# minimega.net
KiCad netlist of a schematic drawn in EAGLE
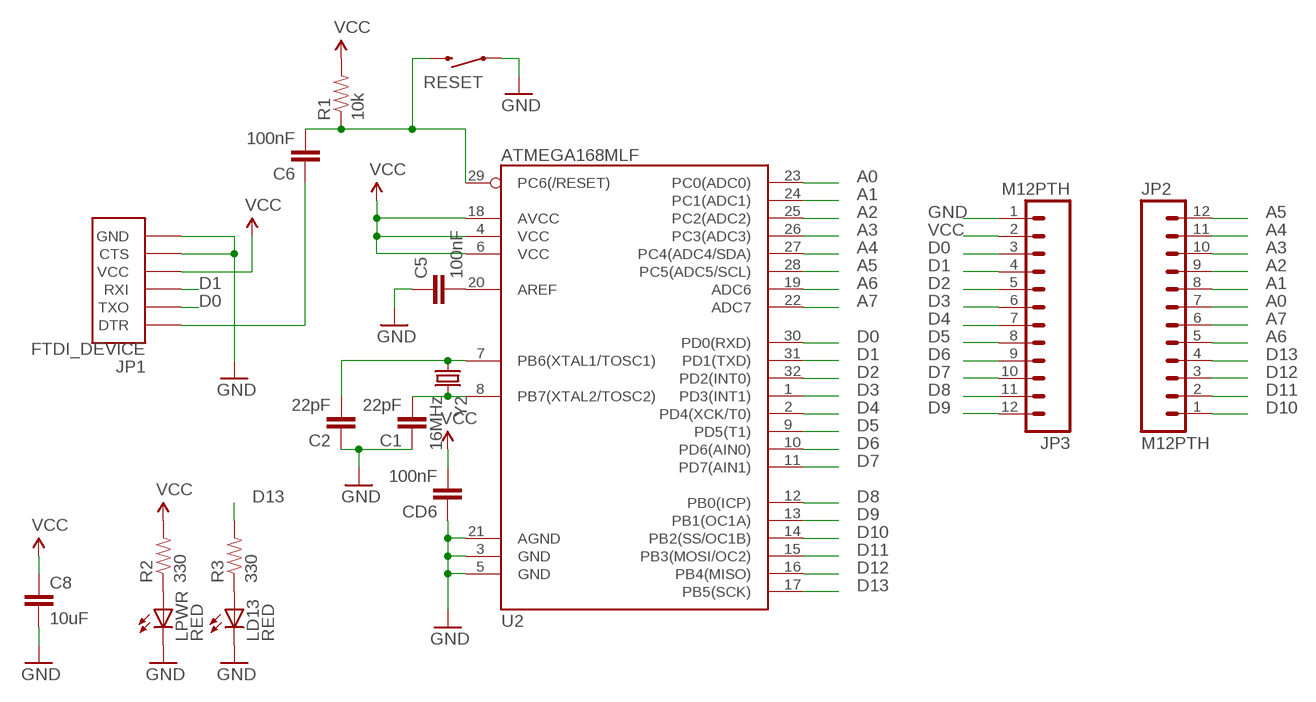
[diagram p0: schematic, sheet 1]

(export (version "E")
  (design (tool "Eeschema 10.0.6"))
  (components
    (comp (ref "C1")
      (value "22pF")
      (footprint "eagle-import:0402-CAP")
      (libsource (lib "eagle-import") (part "10NF-CER"))
    )
    (comp (ref "C2")
      (value "22pF")
      (footprint "eagle-import:0402-CAP")
      (libsource (lib "eagle-import") (part "10NF-CER"))
    )
    (comp (ref "C5")
      (value "100nF")
      (footprint "eagle-import:0402-CAP")
      (libsource (lib "eagle-import") (part "10NF-CER"))
    )
    (comp (ref "C6")
      (value "100nF")
      (footprint "eagle-import:0402-CAP")
      (libsource (lib "eagle-import") (part "10NF-CER"))
    )
    (comp (ref "C8")
      (value "10uF")
      (footprint "eagle-import:0805")
      (libsource (lib "eagle-import") (part "CAP0805"))
    )
    (comp (ref "CD6")
      (value "100nF")
      (footprint "eagle-import:0402-CAP")
      (libsource (lib "eagle-import") (part "10NF-CER"))
    )
    (comp (ref "JP1")
      (value "FTDI_DEVICE")
      (footprint "eagle-import:FTDI_DEVICE_SIDE")
      (libsource (lib "eagle-import") (part "FTDI_DEVICE"))
    )
    (comp (ref "JP2")
      (value "M12PTH")
      (footprint "eagle-import:1X12")
      (libsource (lib "eagle-import") (part "M12PTH"))
    )
    (comp (ref "JP3")
      (value "M12PTH")
      (footprint "eagle-import:1X12")
      (libsource (lib "eagle-import") (part "M12PTH"))
    )
    (comp (ref "LD13")
      (value "RED")
      (footprint "eagle-import:LED-0603")
      (libsource (lib "eagle-import") (part "LED-RED0603"))
    )
    (comp (ref "LPWR")
      (value "RED")
      (footprint "eagle-import:LED-0603")
      (libsource (lib "eagle-import") (part "LED-RED0603"))
    )
    (comp (ref "R1")
      (value "10k")
      (footprint "eagle-import:0603-RES")
      (libsource (lib "eagle-import") (part "RESISTOR0603"))
    )
    (comp (ref "R2")
      (value "330")
      (footprint "eagle-import:0603-RES")
      (libsource (lib "eagle-import") (part "RESISTOR0603"))
    )
    (comp (ref "R3")
      (value "330")
      (footprint "eagle-import:0603-RES")
      (libsource (lib "eagle-import") (part "RESISTOR0603"))
    )
    (comp (ref "RESET")
      (value "SWITCH-MOMENTARY-2PTH")
      (footprint "eagle-import:TACTILE-PTH")
      (libsource (lib "eagle-import") (part "SWITCH-MOMENTARY-2PTH"))
    )
    (comp (ref "U2")
      (value "ATMEGA168MLF")
      (footprint "eagle-import:MLF32")
      (libsource (lib "eagle-import") (part "ATMEGA168MLF"))
    )
    (comp (ref "Y2")
      (value "16MHz")
      (footprint "eagle-import:HC49UP")
      (libsource (lib "eagle-import") (part "CRYSTALSMD"))
    )
  )
  (nets
    (net (code "1") (name "/A0") (class "Default")
      (node (ref "JP2") (pin "7") (pinfunction "7_7") (pintype "passive"))
      (node (ref "U2") (pin "23") (pinfunction "PC0(ADC0)_23") (pintype "bidirectional"))
    )
    (net (code "2") (name "/A1") (class "Default")
      (node (ref "JP2") (pin "8") (pinfunction "8_8") (pintype "passive"))
      (node (ref "U2") (pin "24") (pinfunction "PC1(ADC1)_24") (pintype "bidirectional"))
    )
    (net (code "3") (name "/A2") (class "Default")
      (node (ref "JP2") (pin "9") (pinfunction "9_9") (pintype "passive"))
      (node (ref "U2") (pin "25") (pinfunction "PC2(ADC2)_25") (pintype "bidirectional"))
    )
    (net (code "4") (name "/A3") (class "Default")
      (node (ref "JP2") (pin "10") (pinfunction "10_10") (pintype "passive"))
      (node (ref "U2") (pin "26") (pinfunction "PC3(ADC3)_26") (pintype "bidirectional"))
    )
    (net (code "5") (name "/A4") (class "Default")
      (node (ref "JP2") (pin "11") (pinfunction "11_11") (pintype "passive"))
      (node (ref "U2") (pin "27") (pinfunction "PC4(ADC4/SDA)_27") (pintype "bidirectional"))
    )
    (net (code "6") (name "/A5") (class "Default")
      (node (ref "JP2") (pin "12") (pinfunction "12_12") (pintype "passive"))
      (node (ref "U2") (pin "28") (pinfunction "PC5(ADC5/SCL)_28") (pintype "bidirectional"))
    )
    (net (code "7") (name "/A6") (class "Default")
      (node (ref "JP2") (pin "5") (pinfunction "5_5") (pintype "passive"))
      (node (ref "U2") (pin "19") (pinfunction "ADC6_19") (pintype "bidirectional"))
    )
    (net (code "8") (name "/A7") (class "Default")
      (node (ref "JP2") (pin "6") (pinfunction "6_6") (pintype "passive"))
      (node (ref "U2") (pin "22") (pinfunction "ADC7_22") (pintype "bidirectional"))
    )
    (net (code "9") (name "/D0") (class "Default")
      (node (ref "JP1") (pin "P$2") (pinfunction "TXO_P$2") (pintype "bidirectional"))
      (node (ref "JP3") (pin "3") (pinfunction "3_3") (pintype "passive"))
      (node (ref "U2") (pin "30") (pinfunction "PD0(RXD)_30") (pintype "bidirectional"))
    )
    (net (code "10") (name "/D1") (class "Default")
      (node (ref "JP1") (pin "P$3") (pinfunction "RXI_P$3") (pintype "bidirectional"))
      (node (ref "JP3") (pin "4") (pinfunction "4_4") (pintype "passive"))
      (node (ref "U2") (pin "31") (pinfunction "PD1(TXD)_31") (pintype "bidirectional"))
    )
    (net (code "11") (name "/D2") (class "Default")
      (node (ref "JP3") (pin "5") (pinfunction "5_5") (pintype "passive"))
      (node (ref "U2") (pin "32") (pinfunction "PD2(INT0)_32") (pintype "bidirectional"))
    )
    (net (code "12") (name "/D3") (class "Default")
      (node (ref "JP3") (pin "6") (pinfunction "6_6") (pintype "passive"))
      (node (ref "U2") (pin "1") (pinfunction "PD3(INT1)_1") (pintype "bidirectional"))
    )
    (net (code "13") (name "/D4") (class "Default")
      (node (ref "JP3") (pin "7") (pinfunction "7_7") (pintype "passive"))
      (node (ref "U2") (pin "2") (pinfunction "PD4(XCK/T0)_2") (pintype "bidirectional"))
    )
    (net (code "14") (name "/D5") (class "Default")
      (node (ref "JP3") (pin "8") (pinfunction "8_8") (pintype "passive"))
      (node (ref "U2") (pin "9") (pinfunction "PD5(T1)_9") (pintype "bidirectional"))
    )
    (net (code "15") (name "/D6") (class "Default")
      (node (ref "JP3") (pin "9") (pinfunction "9_9") (pintype "passive"))
      (node (ref "U2") (pin "10") (pinfunction "PD6(AIN0)_10") (pintype "bidirectional"))
    )
    (net (code "16") (name "/D7") (class "Default")
      (node (ref "JP3") (pin "10") (pinfunction "10_10") (pintype "passive"))
      (node (ref "U2") (pin "11") (pinfunction "PD7(AIN1)_11") (pintype "bidirectional"))
    )
    (net (code "17") (name "/D8") (class "Default")
      (node (ref "JP3") (pin "11") (pinfunction "11_11") (pintype "passive"))
      (node (ref "U2") (pin "12") (pinfunction "PB0(ICP)_12") (pintype "bidirectional"))
    )
    (net (code "18") (name "/D9") (class "Default")
      (node (ref "JP3") (pin "12") (pinfunction "12_12") (pintype "passive"))
      (node (ref "U2") (pin "13") (pinfunction "PB1(OC1A)_13") (pintype "bidirectional"))
    )
    (net (code "19") (name "/D10") (class "Default")
      (node (ref "JP2") (pin "1") (pinfunction "1_1") (pintype "passive"))
      (node (ref "U2") (pin "14") (pinfunction "PB2(SS/OC1B)_14") (pintype "bidirectional"))
    )
    (net (code "20") (name "/D11") (class "Default")
      (node (ref "JP2") (pin "2") (pinfunction "2_2") (pintype "passive"))
      (node (ref "U2") (pin "15") (pinfunction "PB3(MOSI/OC2)_15") (pintype "bidirectional"))
    )
    (net (code "21") (name "/D12") (class "Default")
      (node (ref "JP2") (pin "3") (pinfunction "3_3") (pintype "passive"))
      (node (ref "U2") (pin "16") (pinfunction "PB4(MISO)_16") (pintype "bidirectional"))
    )
    (net (code "22") (name "/D13") (class "Default")
      (node (ref "JP2") (pin "4") (pinfunction "4_4") (pintype "passive"))
      (node (ref "R3") (pin "2") (pinfunction "2_2") (pintype "passive"))
      (node (ref "U2") (pin "17") (pinfunction "PB5(SCK)_17") (pintype "bidirectional"))
    )
    (net (code "23") (name "GND") (class "Default")
      (node (ref "C1") (pin "1") (pinfunction "1_1") (pintype "passive"))
      (node (ref "C2") (pin "1") (pinfunction "1_1") (pintype "passive"))
      (node (ref "C5") (pin "1") (pinfunction "1_1") (pintype "passive"))
      (node (ref "C8") (pin "2") (pinfunction "2_2") (pintype "passive"))
      (node (ref "CD6") (pin "1") (pinfunction "1_1") (pintype "passive"))
      (node (ref "JP1") (pin "P$5") (pinfunction "CTS_P$5") (pintype "bidirectional"))
      (node (ref "JP1") (pin "P$6") (pinfunction "GND_P$6") (pintype "bidirectional"))
      (node (ref "JP3") (pin "1") (pinfunction "1_1") (pintype "passive"))
      (node (ref "LD13") (pin "C") (pinfunction "C_C") (pintype "passive"))
      (node (ref "LPWR") (pin "C") (pinfunction "C_C") (pintype "passive"))
      (node (ref "RESET") (pin "1") (pinfunction "1_1") (pintype "passive"))
      (node (ref "U2") (pin "21") (pinfunction "AGND_21") (pintype "bidirectional"))
      (node (ref "U2") (pin "3") (pinfunction "GND_3") (pintype "bidirectional"))
      (node (ref "U2") (pin "5") (pinfunction "GND_5") (pintype "bidirectional"))
    )
    (net (code "24") (name "Net-(JP1-DTR)") (class "Default")
      (node (ref "C6") (pin "1") (pinfunction "1_1") (pintype "passive"))
      (node (ref "JP1") (pin "P$1") (pinfunction "DTR_P$1") (pintype "bidirectional"))
    )
    (net (code "25") (name "Net-(LD13-PadA)") (class "Default")
      (node (ref "LD13") (pin "A") (pinfunction "A_A") (pintype "passive"))
      (node (ref "R3") (pin "1") (pinfunction "1_1") (pintype "passive"))
    )
    (net (code "26") (name "Net-(LPWR-PadA)") (class "Default")
      (node (ref "LPWR") (pin "A") (pinfunction "A_A") (pintype "passive"))
      (node (ref "R2") (pin "1") (pinfunction "1_1") (pintype "passive"))
    )
    (net (code "27") (name "Net-(RESET-2)") (class "Default")
      (node (ref "C6") (pin "2") (pinfunction "2_2") (pintype "passive"))
      (node (ref "R1") (pin "1") (pinfunction "1_1") (pintype "passive"))
      (node (ref "RESET") (pin "3") (pinfunction "2_3") (pintype "passive"))
      (node (ref "U2") (pin "29") (pinfunction "PC6(/RESET)_29") (pintype "bidirectional"))
    )
    (net (code "28") (name "Net-(U2-AREF)") (class "Default")
      (node (ref "C5") (pin "2") (pinfunction "2_2") (pintype "passive"))
      (node (ref "U2") (pin "20") (pinfunction "AREF_20") (pintype "bidirectional"))
    )
    (net (code "29") (name "Net-(U2-PB6(XTAL1{slash}TOSC1))") (class "Default")
      (node (ref "C2") (pin "2") (pinfunction "2_2") (pintype "passive"))
      (node (ref "U2") (pin "7") (pinfunction "PB6(XTAL1/TOSC1)_7") (pintype "bidirectional"))
      (node (ref "Y2") (pin "1") (pinfunction "1_1") (pintype "passive"))
    )
    (net (code "30") (name "Net-(U2-PB7(XTAL2{slash}TOSC2))") (class "Default")
      (node (ref "C1") (pin "2") (pinfunction "2_2") (pintype "passive"))
      (node (ref "U2") (pin "8") (pinfunction "PB7(XTAL2/TOSC2)_8") (pintype "bidirectional"))
      (node (ref "Y2") (pin "2") (pinfunction "2_2") (pintype "passive"))
    )
    (net (code "31") (name "VCC") (class "Default")
      (node (ref "C8") (pin "1") (pinfunction "1_1") (pintype "passive"))
      (node (ref "CD6") (pin "2") (pinfunction "2_2") (pintype "passive"))
      (node (ref "JP1") (pin "P$4") (pinfunction "VCC_P$4") (pintype "bidirectional"))
      (node (ref "JP3") (pin "2") (pinfunction "2_2") (pintype "passive"))
      (node (ref "R1") (pin "2") (pinfunction "2_2") (pintype "passive"))
      (node (ref "R2") (pin "2") (pinfunction "2_2") (pintype "passive"))
      (node (ref "U2") (pin "18") (pinfunction "AVCC_18") (pintype "bidirectional"))
      (node (ref "U2") (pin "4") (pinfunction "VCC_4") (pintype "bidirectional"))
      (node (ref "U2") (pin "6") (pinfunction "VCC_6") (pintype "bidirectional"))
    )
  )
)
